# golden.net
KiCad netlist of a schematic drawn in EAGLE
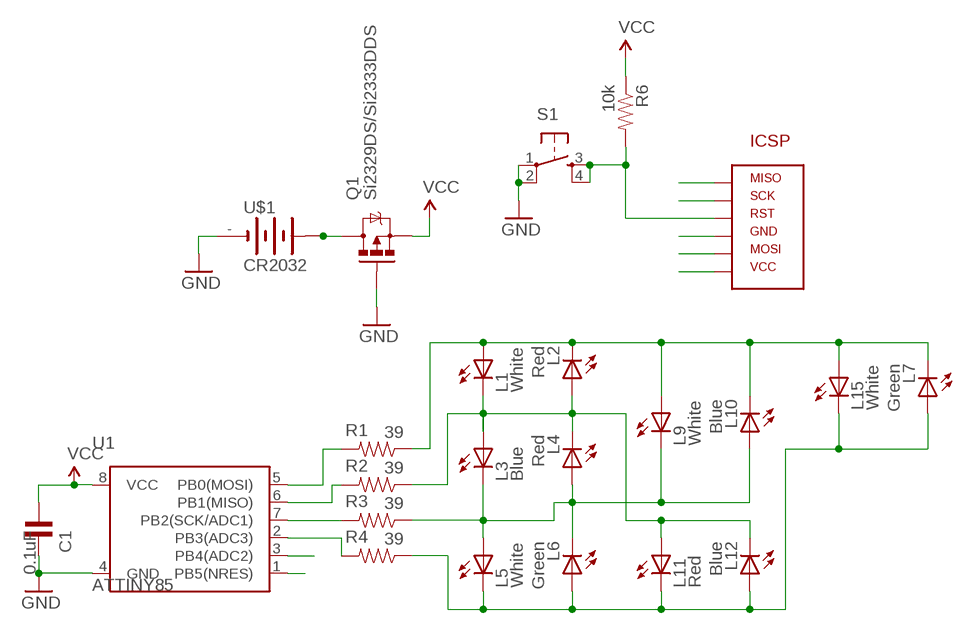
[diagram p0: schematic, sheet 1]

(export (version "E")
  (design (tool "Eeschema 10.0.6"))
  (components
    (comp (ref "C1")
      (value "0.1uF")
      (footprint "eagle-import:C0805")
      (libsource (lib "eagle-import") (part "CAPACITOR0805"))
    )
    (comp (ref "L1")
      (value "White")
      (footprint "eagle-import:LED-0805")
      (libsource (lib "eagle-import") (part "LED0805"))
    )
    (comp (ref "L2")
      (value "Red")
      (footprint "eagle-import:LED-0805")
      (libsource (lib "eagle-import") (part "LED0805"))
    )
    (comp (ref "L3")
      (value "Blue")
      (footprint "eagle-import:LED-0805")
      (libsource (lib "eagle-import") (part "LED0805"))
    )
    (comp (ref "L4")
      (value "Red")
      (footprint "eagle-import:LED-0805")
      (libsource (lib "eagle-import") (part "LED0805"))
    )
    (comp (ref "L5")
      (value "White")
      (footprint "eagle-import:LED-0805")
      (libsource (lib "eagle-import") (part "LED0805"))
    )
    (comp (ref "L6")
      (value "Green")
      (footprint "eagle-import:LED-0805")
      (libsource (lib "eagle-import") (part "LED0805"))
    )
    (comp (ref "L7")
      (value "Green")
      (footprint "eagle-import:LED-0805")
      (libsource (lib "eagle-import") (part "LED0805"))
    )
    (comp (ref "L9")
      (value "White")
      (footprint "eagle-import:LED-0805")
      (libsource (lib "eagle-import") (part "LED0805"))
    )
    (comp (ref "L10")
      (value "Blue")
      (footprint "eagle-import:LED-0805")
      (libsource (lib "eagle-import") (part "LED0805"))
    )
    (comp (ref "L11")
      (value "Red")
      (footprint "eagle-import:LED-0805")
      (libsource (lib "eagle-import") (part "LED0805"))
    )
    (comp (ref "L12")
      (value "Blue")
      (footprint "eagle-import:LED-0805")
      (libsource (lib "eagle-import") (part "LED0805"))
    )
    (comp (ref "L15")
      (value "White")
      (footprint "eagle-import:LED-0805")
      (libsource (lib "eagle-import") (part "LED0805"))
    )
    (comp (ref "Q1")
      (value "Si2329DS/Si2333DDS")
      (footprint "eagle-import:SOT23-3A")
      (libsource (lib "eagle-import") (part "MOSFET_P_CH"))
    )
    (comp (ref "R1")
      (value "39")
      (footprint "eagle-import:R0805")
      (libsource (lib "eagle-import") (part "RESISTORR0805-SMD"))
    )
    (comp (ref "R2")
      (value "39")
      (footprint "eagle-import:R0805")
      (libsource (lib "eagle-import") (part "RESISTORR0805-SMD"))
    )
    (comp (ref "R3")
      (value "39")
      (footprint "eagle-import:R0805")
      (libsource (lib "eagle-import") (part "RESISTORR0805-SMD"))
    )
    (comp (ref "R4")
      (value "39")
      (footprint "eagle-import:R0805")
      (libsource (lib "eagle-import") (part "RESISTORR0805-SMD"))
    )
    (comp (ref "R6")
      (value "10k")
      (footprint "eagle-import:R0805")
      (libsource (lib "eagle-import") (part "RESISTORR0805-SMD"))
    )
    (comp (ref "S1")
      (value "TAC_SWITCHSMD")
      (footprint "eagle-import:TACTILE_SWITCH_SMD")
      (libsource (lib "eagle-import") (part "TAC_SWITCHSMD"))
    )
    (comp (ref "U$1")
      (value "CR2032")
      (footprint "eagle-import:BAT-HLD-001")
      (libsource (lib "eagle-import") (part "BAT-HLD-001"))
    )
    (comp (ref "U$2")
      (value "AVR_ICSP_6P1X6")
      (footprint "eagle-import:AVR_ICSP_1X6_SMD")
      (libsource (lib "eagle-import") (part "AVR_ICSP_6P1X6"))
    )
    (comp (ref "U1")
      (value "ATTINY85")
      (footprint "eagle-import:SOIC-8")
      (libsource (lib "eagle-import") (part "ATTINY85"))
    )
  )
  (nets
    (net (code "1") (name "/MISO") (class "Default")
      (node (ref "R2") (pin "2") (pinfunction "2_2") (pintype "passive"))
      (node (ref "U$2") (pin "P5") (pinfunction "MISO_P5") (pintype "bidirectional"))
      (node (ref "U1") (pin "6") (pinfunction "PB1(MISO)_6") (pintype "bidirectional"))
    )
    (net (code "2") (name "/MOSI") (class "Default")
      (node (ref "R1") (pin "2") (pinfunction "2_2") (pintype "passive"))
      (node (ref "U$2") (pin "P4") (pinfunction "MOSI_P4") (pintype "bidirectional"))
      (node (ref "U1") (pin "5") (pinfunction "PB0(MOSI)_5") (pintype "bidirectional"))
    )
    (net (code "3") (name "/RST") (class "Default")
      (node (ref "R6") (pin "2") (pinfunction "2_2") (pintype "passive"))
      (node (ref "S1") (pin "3") (pinfunction "3_3") (pintype "passive"))
      (node (ref "S1") (pin "4") (pinfunction "4_4") (pintype "passive"))
      (node (ref "U$2") (pin "P3") (pinfunction "RST_P3") (pintype "bidirectional"))
      (node (ref "U1") (pin "1") (pinfunction "PB5(NRES)_1") (pintype "bidirectional"))
    )
    (net (code "4") (name "/SCK") (class "Default")
      (node (ref "R3") (pin "2") (pinfunction "2_2") (pintype "passive"))
      (node (ref "U$2") (pin "P2") (pinfunction "SCK_P2") (pintype "bidirectional"))
      (node (ref "U1") (pin "7") (pinfunction "PB2(SCK/ADC1)_7") (pintype "bidirectional"))
    )
    (net (code "5") (name "GND") (class "Default")
      (node (ref "C1") (pin "2") (pinfunction "2_2") (pintype "passive"))
      (node (ref "Q1") (pin "1") (pinfunction "G_1") (pintype "passive"))
      (node (ref "S1") (pin "1") (pinfunction "1_1") (pintype "passive"))
      (node (ref "S1") (pin "2") (pinfunction "2_2") (pintype "passive"))
      (node (ref "U$1") (pin "-") (pinfunction "-_-") (pintype "passive"))
      (node (ref "U$2") (pin "P6") (pinfunction "GND_P6") (pintype "bidirectional"))
      (node (ref "U1") (pin "4") (pinfunction "GND_4") (pintype "bidirectional"))
    )
    (net (code "6") (name "Net-(L1-PadA)") (class "Default")
      (node (ref "L1") (pin "A") (pinfunction "A_A") (pintype "passive"))
      (node (ref "L10") (pin "C") (pinfunction "C_C") (pintype "passive"))
      (node (ref "L15") (pin "A") (pinfunction "A_A") (pintype "passive"))
      (node (ref "L2") (pin "C") (pinfunction "C_C") (pintype "passive"))
      (node (ref "L7") (pin "C") (pinfunction "C_C") (pintype "passive"))
      (node (ref "L9") (pin "A") (pinfunction "A_A") (pintype "passive"))
      (node (ref "R1") (pin "1") (pinfunction "1_1") (pintype "passive"))
    )
    (net (code "7") (name "Net-(L1-PadC)") (class "Default")
      (node (ref "L1") (pin "C") (pinfunction "C_C") (pintype "passive"))
      (node (ref "L11") (pin "A") (pinfunction "A_A") (pintype "passive"))
      (node (ref "L12") (pin "C") (pinfunction "C_C") (pintype "passive"))
      (node (ref "L2") (pin "A") (pinfunction "A_A") (pintype "passive"))
      (node (ref "L3") (pin "A") (pinfunction "A_A") (pintype "passive"))
      (node (ref "L4") (pin "C") (pinfunction "C_C") (pintype "passive"))
      (node (ref "R2") (pin "1") (pinfunction "1_1") (pintype "passive"))
    )
    (net (code "8") (name "Net-(L10-PadA)") (class "Default")
      (node (ref "L10") (pin "A") (pinfunction "A_A") (pintype "passive"))
      (node (ref "L3") (pin "C") (pinfunction "C_C") (pintype "passive"))
      (node (ref "L4") (pin "A") (pinfunction "A_A") (pintype "passive"))
      (node (ref "L5") (pin "A") (pinfunction "A_A") (pintype "passive"))
      (node (ref "L6") (pin "C") (pinfunction "C_C") (pintype "passive"))
      (node (ref "L9") (pin "C") (pinfunction "C_C") (pintype "passive"))
      (node (ref "R3") (pin "1") (pinfunction "1_1") (pintype "passive"))
    )
    (net (code "9") (name "Net-(L11-PadC)") (class "Default")
      (node (ref "L11") (pin "C") (pinfunction "C_C") (pintype "passive"))
      (node (ref "L12") (pin "A") (pinfunction "A_A") (pintype "passive"))
      (node (ref "L15") (pin "C") (pinfunction "C_C") (pintype "passive"))
      (node (ref "L5") (pin "C") (pinfunction "C_C") (pintype "passive"))
      (node (ref "L6") (pin "A") (pinfunction "A_A") (pintype "passive"))
      (node (ref "L7") (pin "A") (pinfunction "A_A") (pintype "passive"))
      (node (ref "R4") (pin "1") (pinfunction "1_1") (pintype "passive"))
    )
    (net (code "10") (name "Net-(Q1-D)") (class "Default")
      (node (ref "Q1") (pin "3") (pinfunction "D_3") (pintype "passive"))
      (node (ref "U$1") (pin "+@1") (pinfunction "+_+@1") (pintype "passive"))
      (node (ref "U$1") (pin "+@2") (pinfunction "+_+@2") (pintype "passive"))
    )
    (net (code "11") (name "Net-(U1-PB3(ADC3))") (class "Default")
      (node (ref "R4") (pin "2") (pinfunction "2_2") (pintype "passive"))
      (node (ref "U1") (pin "2") (pinfunction "PB3(ADC3)_2") (pintype "bidirectional"))
    )
    (net (code "12") (name "VCC") (class "Default")
      (node (ref "C1") (pin "1") (pinfunction "1_1") (pintype "passive"))
      (node (ref "Q1") (pin "2") (pinfunction "S_2") (pintype "passive"))
      (node (ref "R6") (pin "1") (pinfunction "1_1") (pintype "passive"))
      (node (ref "U$2") (pin "P1") (pinfunction "VCC_P1") (pintype "bidirectional"))
      (node (ref "U1") (pin "8") (pinfunction "VCC_8") (pintype "bidirectional"))
    )
    (net (code "13") (name "unconnected-(U1-PB4(ADC2)-Pad3)") (class "Default")
      (node (ref "U1") (pin "3") (pinfunction "PB4(ADC2)_3") (pintype "bidirectional"))
    )
  )
)
